# Vboost.net
KiCad netlist of a schematic drawn in EAGLE
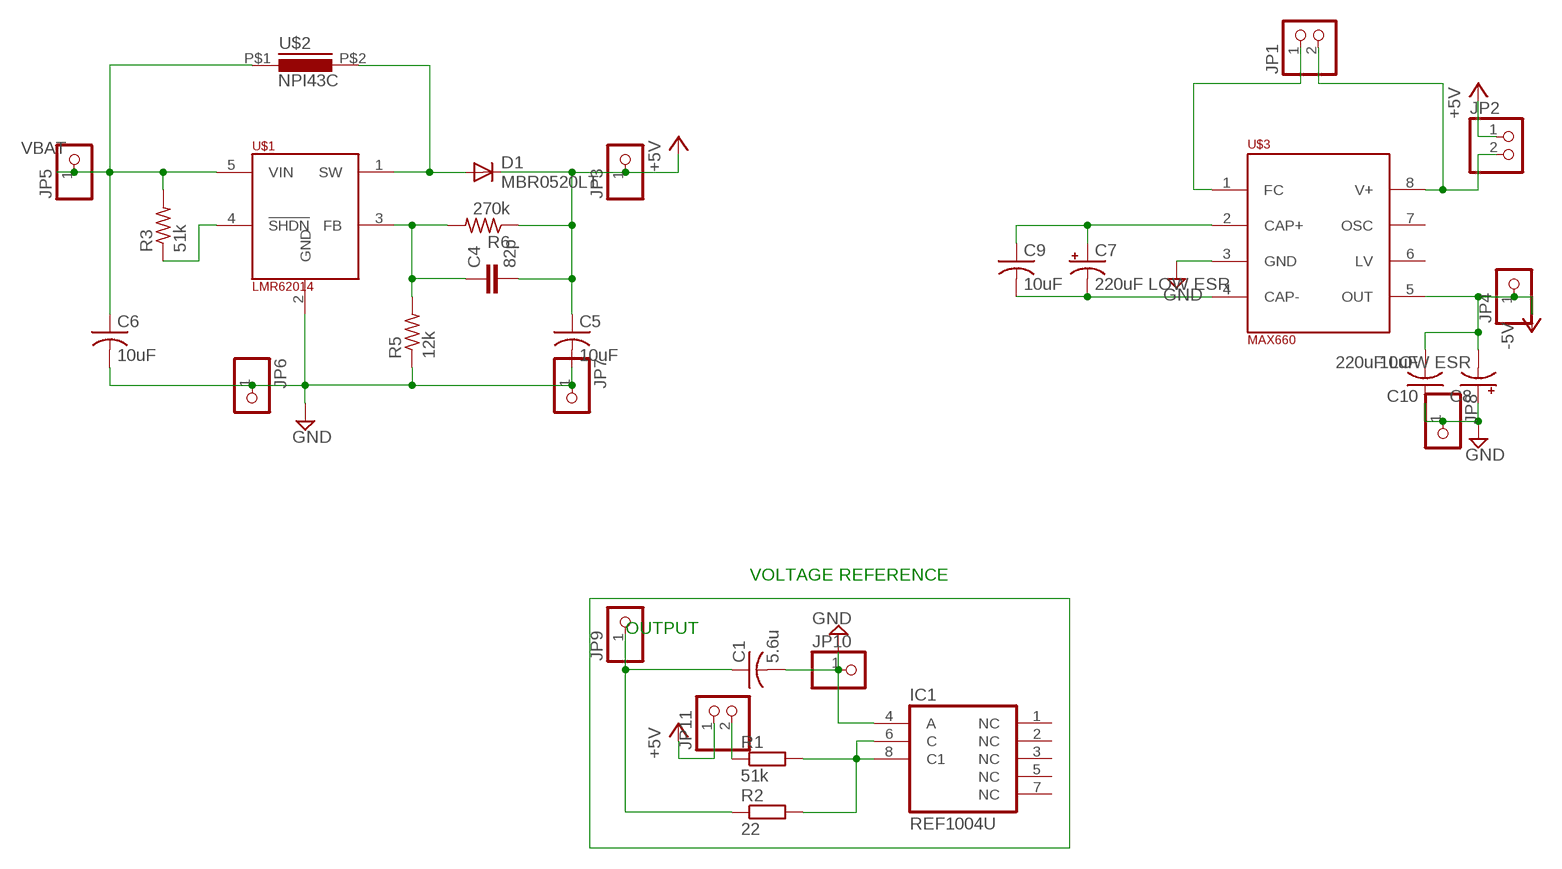
[diagram p0: schematic, sheet 1]

(export (version "E")
  (design (tool "Eeschema 10.0.6"))
  (components
    (comp (ref "C1")
      (value "5.6u")
      (footprint "eagle-import:C0805K")
      (libsource (lib "eagle-import") (part "C-USC0805K"))
    )
    (comp (ref "C4")
      (value "82p")
      (footprint "eagle-import:C0805")
      (libsource (lib "eagle-import") (part "C-EUC0805"))
    )
    (comp (ref "C5")
      (value "10uF")
      (footprint "eagle-import:C0805")
      (libsource (lib "eagle-import") (part "resistor_C-USC0805"))
    )
    (comp (ref "C6")
      (value "10uF")
      (footprint "eagle-import:C0805")
      (libsource (lib "eagle-import") (part "resistor_C-USC0805"))
    )
    (comp (ref "C7")
      (value "220uF LOW ESR")
      (footprint "eagle-import:PANASONIC_D")
      (libsource (lib "eagle-import") (part "CPOL-USD"))
    )
    (comp (ref "C8")
      (value "220uF LOW ESR")
      (footprint "eagle-import:PANASONIC_D")
      (libsource (lib "eagle-import") (part "CPOL-USD"))
    )
    (comp (ref "C9")
      (value "10uF")
      (footprint "eagle-import:C0805")
      (libsource (lib "eagle-import") (part "resistor_C-USC0805"))
    )
    (comp (ref "C10")
      (value "10uF")
      (footprint "eagle-import:C0805")
      (libsource (lib "eagle-import") (part "resistor_C-USC0805"))
    )
    (comp (ref "D1")
      (value "MBR0520LT")
      (footprint "eagle-import:SOD123")
      (libsource (lib "eagle-import") (part "MBR0520LT"))
    )
    (comp (ref "IC1")
      (value "REF1004U")
      (footprint "eagle-import:SO08")
      (fields (field (name "MF") "TEXAS INSTRUMENTS") (field (name "MPN") "REF1004C-1.2"))
      (libsource (lib "eagle-import") (part "REF1004U"))
    )
    (comp (ref "JP1")
      (value "PINHD-1X2")
      (footprint "eagle-import:1X02")
      (libsource (lib "eagle-import") (part "PINHD-1X2"))
    )
    (comp (ref "JP2")
      (value "PINHD-1X2")
      (footprint "eagle-import:1X02")
      (libsource (lib "eagle-import") (part "PINHD-1X2"))
    )
    (comp (ref "JP3")
      (value "PINHD-1X1")
      (footprint "eagle-import:1X01")
      (libsource (lib "eagle-import") (part "PINHD-1X1"))
    )
    (comp (ref "JP4")
      (value "PINHD-1X1")
      (footprint "eagle-import:1X01")
      (libsource (lib "eagle-import") (part "PINHD-1X1"))
    )
    (comp (ref "JP5")
      (value "PINHD-1X1")
      (footprint "eagle-import:1X01")
      (libsource (lib "eagle-import") (part "PINHD-1X1"))
    )
    (comp (ref "JP6")
      (value "PINHD-1X1")
      (footprint "eagle-import:1X01")
      (libsource (lib "eagle-import") (part "PINHD-1X1"))
    )
    (comp (ref "JP7")
      (value "PINHD-1X1")
      (footprint "eagle-import:1X01")
      (libsource (lib "eagle-import") (part "PINHD-1X1"))
    )
    (comp (ref "JP8")
      (value "PINHD-1X1")
      (footprint "eagle-import:1X01")
      (libsource (lib "eagle-import") (part "PINHD-1X1"))
    )
    (comp (ref "JP9")
      (value "PINHD-1X1")
      (footprint "eagle-import:1X01")
      (libsource (lib "eagle-import") (part "PINHD-1X1"))
    )
    (comp (ref "JP10")
      (value "PINHD-1X1")
      (footprint "eagle-import:1X01")
      (libsource (lib "eagle-import") (part "PINHD-1X1"))
    )
    (comp (ref "JP11")
      (value "PINHD-1X2")
      (footprint "eagle-import:1X02")
      (libsource (lib "eagle-import") (part "PINHD-1X2"))
    )
    (comp (ref "R1")
      (value "51k")
      (footprint "eagle-import:M0805")
      (libsource (lib "eagle-import") (part "R-EU_M0805"))
    )
    (comp (ref "R2")
      (value "22")
      (footprint "eagle-import:M0805")
      (libsource (lib "eagle-import") (part "R-EU_M0805"))
    )
    (comp (ref "R3")
      (value "51k")
      (footprint "eagle-import:R0805")
      (libsource (lib "eagle-import") (part "R-US_R0805"))
    )
    (comp (ref "R5")
      (value "12k")
      (footprint "eagle-import:R0805")
      (libsource (lib "eagle-import") (part "R-US_R0805"))
    )
    (comp (ref "R6")
      (value "270k")
      (footprint "eagle-import:R0805")
      (libsource (lib "eagle-import") (part "R-US_R0805"))
    )
    (comp (ref "U$1")
      (value "LMR62014")
      (footprint "eagle-import:SOT23-5")
      (libsource (lib "eagle-import") (part "LMR62014"))
    )
    (comp (ref "U$2")
      (value "NPI43C")
      (footprint "eagle-import:NPI43C")
      (libsource (lib "eagle-import") (part "NPI43C"))
    )
    (comp (ref "U$3")
      (value "MAX660")
      (footprint "eagle-import:SO08")
      (libsource (lib "eagle-import") (part "MAX660"))
    )
  )
  (nets
    (net (code "1") (name "+5V") (class "Default")
      (node (ref "C4") (pin "2") (pinfunction "2_2") (pintype "passive"))
      (node (ref "C5") (pin "1") (pinfunction "1_1") (pintype "passive"))
      (node (ref "D1") (pin "C") (pinfunction "C_C") (pintype "passive"))
      (node (ref "JP11") (pin "1") (pinfunction "1_1") (pintype "passive"))
      (node (ref "JP2") (pin "1") (pinfunction "1_1") (pintype "passive"))
      (node (ref "JP3") (pin "1") (pinfunction "1_1") (pintype "passive"))
      (node (ref "R6") (pin "1") (pinfunction "1_1") (pintype "passive"))
    )
    (net (code "2") (name "-5V") (class "Default")
      (node (ref "C10") (pin "2") (pinfunction "2_2") (pintype "passive"))
      (node (ref "C8") (pin "-") (pinfunction "-_-") (pintype "passive"))
      (node (ref "JP4") (pin "1") (pinfunction "1_1") (pintype "passive"))
      (node (ref "U$3") (pin "5") (pinfunction "OUT_5") (pintype "bidirectional"))
    )
    (net (code "3") (name "/VBAT") (class "Default")
      (node (ref "C6") (pin "1") (pinfunction "1_1") (pintype "passive"))
      (node (ref "JP5") (pin "1") (pinfunction "1_1") (pintype "passive"))
      (node (ref "R3") (pin "2") (pinfunction "2_2") (pintype "passive"))
      (node (ref "U$1") (pin "5") (pinfunction "VIN_5") (pintype "bidirectional"))
      (node (ref "U$2") (pin "P$1") (pinfunction "1_P$1") (pintype "passive"))
    )
    (net (code "4") (name "GND") (class "Default")
      (node (ref "C1") (pin "2") (pinfunction "2_2") (pintype "passive"))
      (node (ref "C10") (pin "1") (pinfunction "1_1") (pintype "passive"))
      (node (ref "C5") (pin "2") (pinfunction "2_2") (pintype "passive"))
      (node (ref "C6") (pin "2") (pinfunction "2_2") (pintype "passive"))
      (node (ref "C8") (pin "+") (pinfunction "+_+") (pintype "passive"))
      (node (ref "IC1") (pin "4") (pinfunction "A_4") (pintype "passive"))
      (node (ref "JP10") (pin "1") (pinfunction "1_1") (pintype "passive"))
      (node (ref "JP6") (pin "1") (pinfunction "1_1") (pintype "passive"))
      (node (ref "JP7") (pin "1") (pinfunction "1_1") (pintype "passive"))
      (node (ref "JP8") (pin "1") (pinfunction "1_1") (pintype "passive"))
      (node (ref "R5") (pin "1") (pinfunction "1_1") (pintype "passive"))
      (node (ref "U$1") (pin "2") (pinfunction "GND_2") (pintype "bidirectional"))
      (node (ref "U$3") (pin "3") (pinfunction "GND_3") (pintype "bidirectional"))
    )
    (net (code "5") (name "Net-(C1-Pad1)") (class "Default")
      (node (ref "C1") (pin "1") (pinfunction "1_1") (pintype "passive"))
      (node (ref "JP9") (pin "1") (pinfunction "1_1") (pintype "passive"))
      (node (ref "R2") (pin "1") (pinfunction "1_1") (pintype "passive"))
    )
    (net (code "6") (name "Net-(IC1-C)") (class "Default")
      (node (ref "IC1") (pin "6") (pinfunction "C_6") (pintype "passive"))
      (node (ref "IC1") (pin "8") (pinfunction "C1_8") (pintype "passive"))
      (node (ref "R1") (pin "2") (pinfunction "2_2") (pintype "passive"))
      (node (ref "R2") (pin "2") (pinfunction "2_2") (pintype "passive"))
    )
    (net (code "7") (name "Net-(JP11-Pad2)") (class "Default")
      (node (ref "JP11") (pin "2") (pinfunction "2_2") (pintype "passive"))
      (node (ref "R1") (pin "1") (pinfunction "1_1") (pintype "passive"))
    )
    (net (code "8") (name "Net-(U$1-FB)") (class "Default")
      (node (ref "C4") (pin "1") (pinfunction "1_1") (pintype "passive"))
      (node (ref "R5") (pin "2") (pinfunction "2_2") (pintype "passive"))
      (node (ref "R6") (pin "2") (pinfunction "2_2") (pintype "passive"))
      (node (ref "U$1") (pin "3") (pinfunction "FB_3") (pintype "bidirectional"))
    )
    (net (code "9") (name "Net-(U$1-SW)") (class "Default")
      (node (ref "D1") (pin "A") (pinfunction "A_A") (pintype "passive"))
      (node (ref "U$1") (pin "1") (pinfunction "SW_1") (pintype "bidirectional"))
      (node (ref "U$2") (pin "P$2") (pinfunction "2_P$2") (pintype "passive"))
    )
    (net (code "10") (name "Net-(U$1-~{SHDN})") (class "Default")
      (node (ref "R3") (pin "1") (pinfunction "1_1") (pintype "passive"))
      (node (ref "U$1") (pin "4") (pinfunction "~{SHDN}_4") (pintype "bidirectional"))
    )
    (net (code "11") (name "Net-(U$3-CAP+)") (class "Default")
      (node (ref "C7") (pin "+") (pinfunction "+_+") (pintype "passive"))
      (node (ref "C9") (pin "1") (pinfunction "1_1") (pintype "passive"))
      (node (ref "U$3") (pin "2") (pinfunction "CAP+_2") (pintype "bidirectional"))
    )
    (net (code "12") (name "Net-(U$3-CAP-)") (class "Default")
      (node (ref "C7") (pin "-") (pinfunction "-_-") (pintype "passive"))
      (node (ref "C9") (pin "2") (pinfunction "2_2") (pintype "passive"))
      (node (ref "U$3") (pin "4") (pinfunction "CAP-_4") (pintype "bidirectional"))
    )
    (net (code "13") (name "Net-(U$3-FC)") (class "Default")
      (node (ref "JP1") (pin "1") (pinfunction "1_1") (pintype "passive"))
      (node (ref "U$3") (pin "1") (pinfunction "FC_1") (pintype "bidirectional"))
    )
    (net (code "14") (name "Net-(U$3-V+)") (class "Default")
      (node (ref "JP1") (pin "2") (pinfunction "2_2") (pintype "passive"))
      (node (ref "JP2") (pin "2") (pinfunction "2_2") (pintype "passive"))
      (node (ref "U$3") (pin "8") (pinfunction "V+_8") (pintype "bidirectional"))
    )
    (net (code "15") (name "unconnected-(IC1-NC-Pad1)") (class "Default")
      (node (ref "IC1") (pin "1") (pinfunction "NC_1") (pintype "no_connect"))
    )
    (net (code "16") (name "unconnected-(IC1-NC-Pad2)") (class "Default")
      (node (ref "IC1") (pin "2") (pinfunction "NC_2") (pintype "no_connect"))
    )
    (net (code "17") (name "unconnected-(IC1-NC-Pad3)") (class "Default")
      (node (ref "IC1") (pin "3") (pinfunction "NC_3") (pintype "no_connect"))
    )
    (net (code "18") (name "unconnected-(IC1-NC-Pad5)") (class "Default")
      (node (ref "IC1") (pin "5") (pinfunction "NC_5") (pintype "no_connect"))
    )
    (net (code "19") (name "unconnected-(IC1-NC-Pad7)") (class "Default")
      (node (ref "IC1") (pin "7") (pinfunction "NC_7") (pintype "no_connect"))
    )
    (net (code "20") (name "unconnected-(U$3-LV-Pad6)") (class "Default")
      (node (ref "U$3") (pin "6") (pinfunction "LV_6") (pintype "bidirectional"))
    )
    (net (code "21") (name "unconnected-(U$3-OSC-Pad7)") (class "Default")
      (node (ref "U$3") (pin "7") (pinfunction "OSC_7") (pintype "bidirectional"))
    )
  )
)
